# com_board.net
KiCad netlist of a schematic drawn in EAGLE
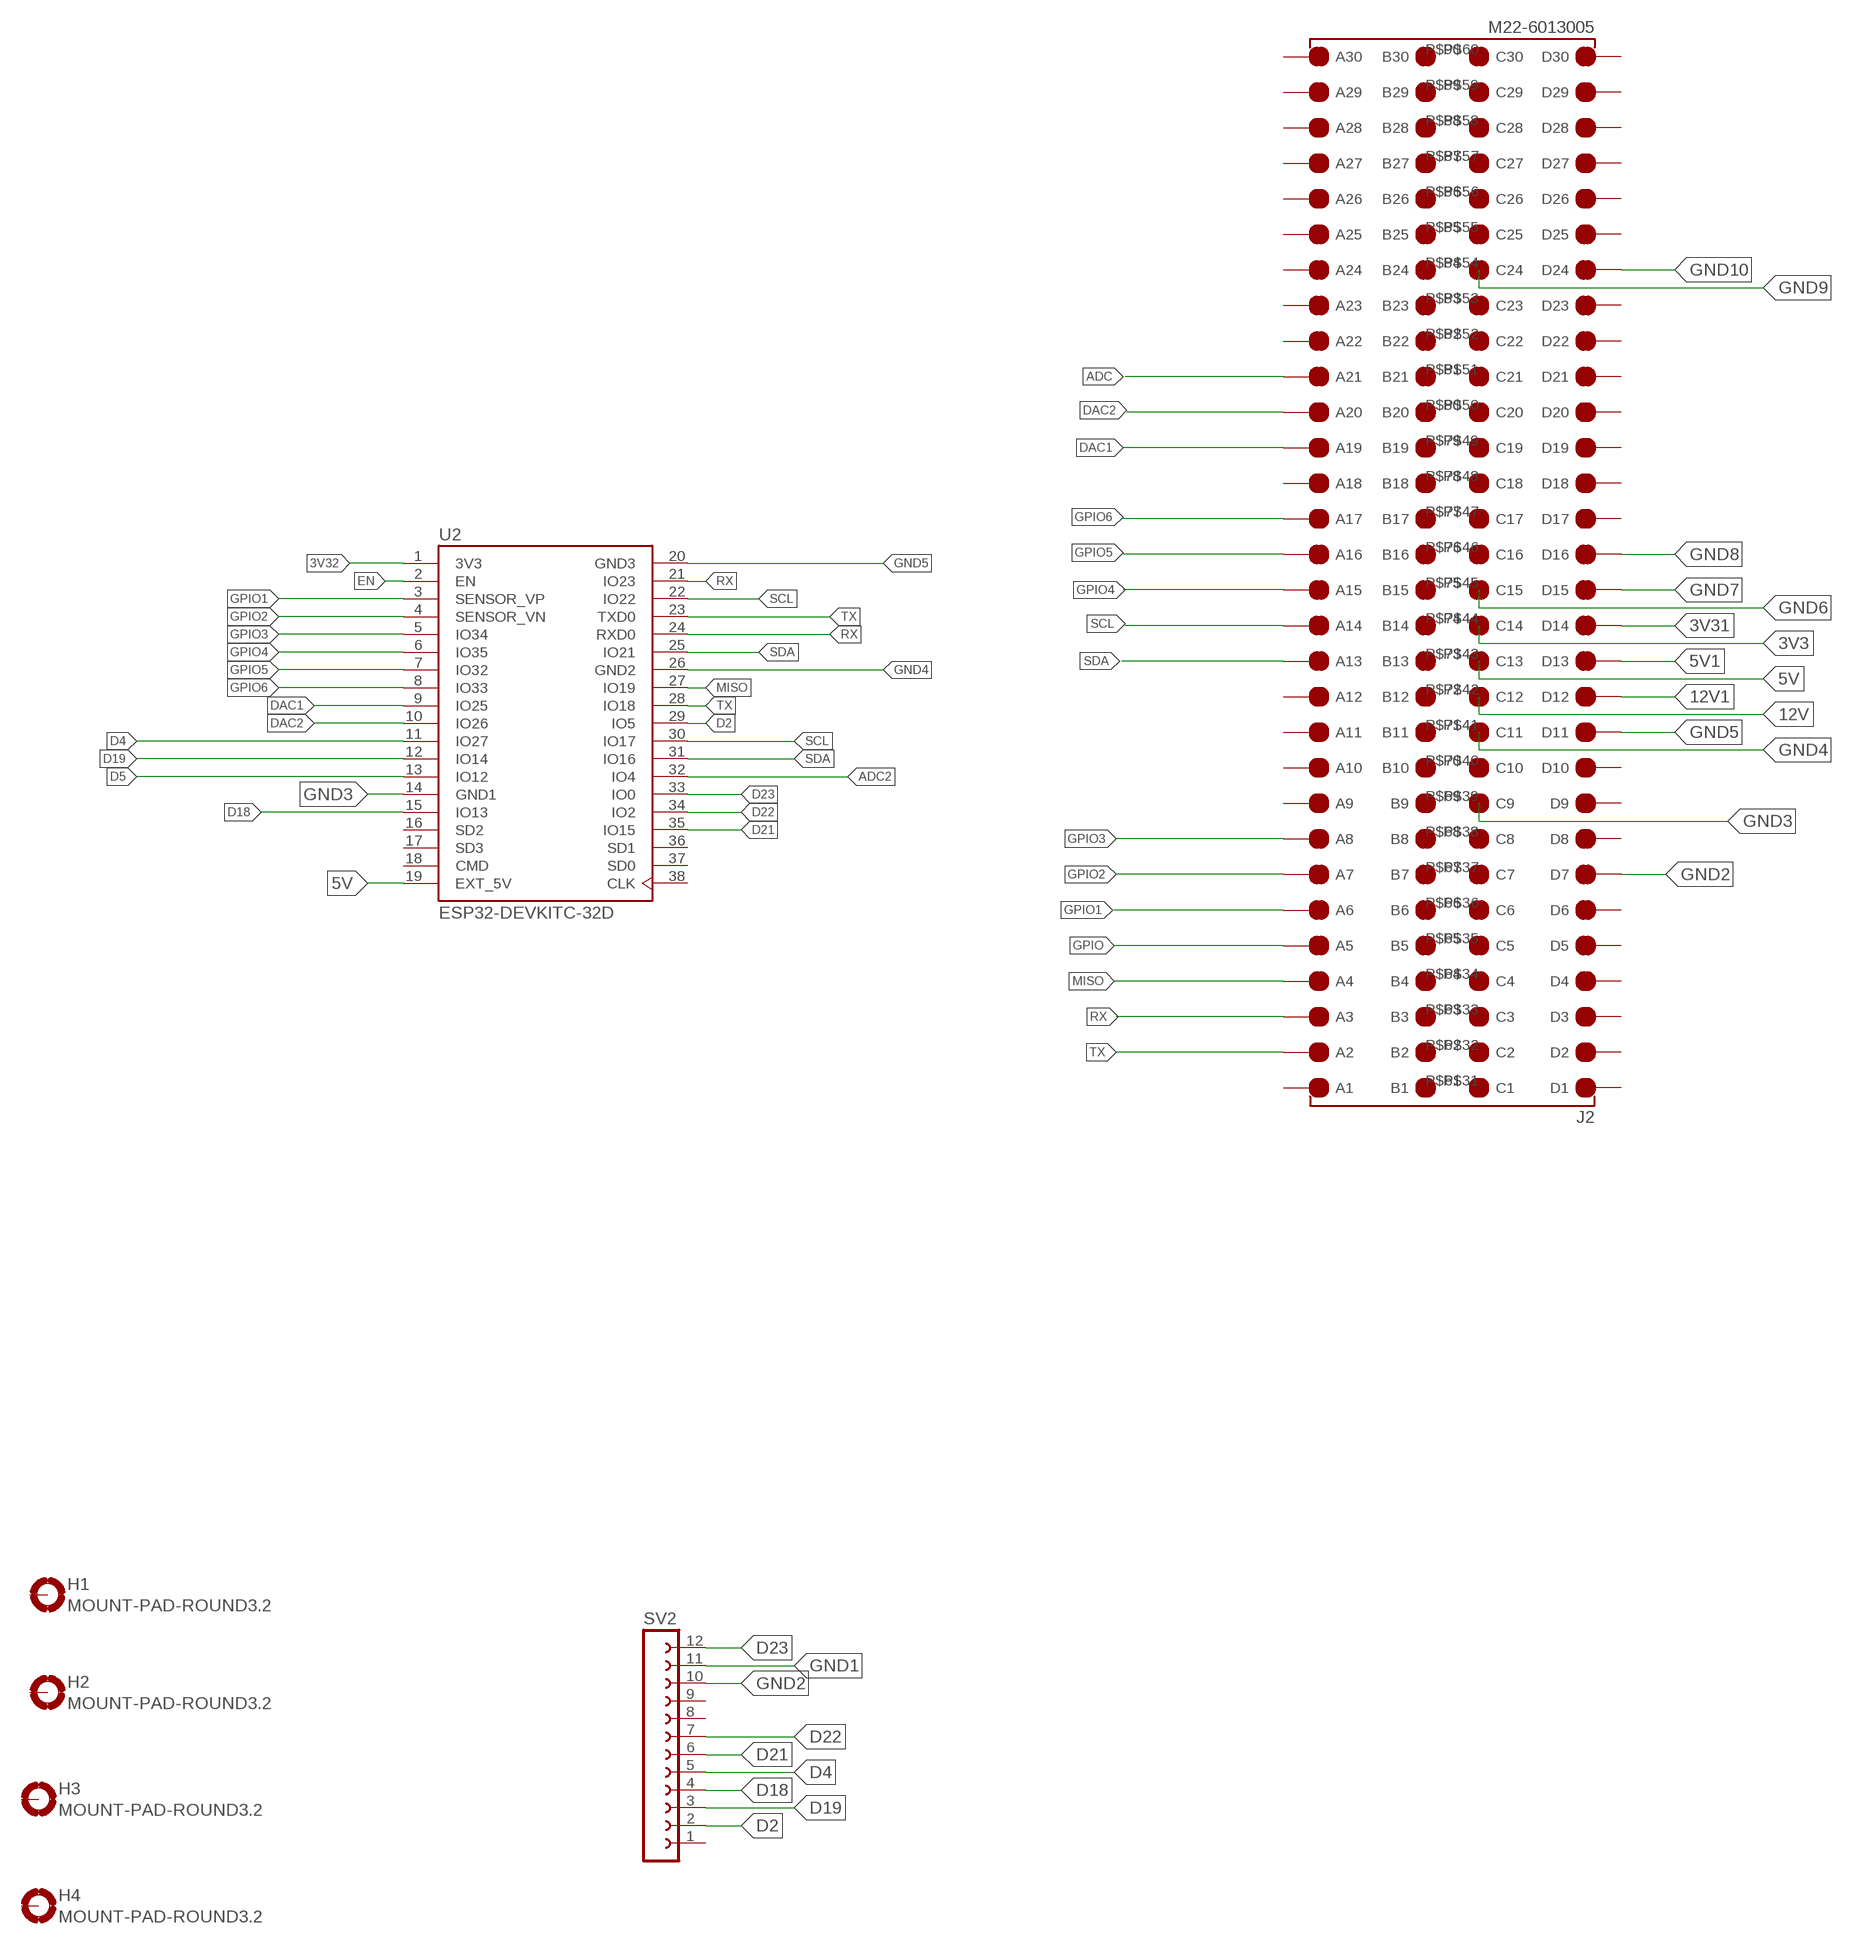
[diagram p0: schematic, sheet 1]

(export (version "E")
  (design (tool "Eeschema 10.0.6"))
  (components
    (comp (ref "H1")
      (value "MOUNT-PAD-ROUND3.2")
      (footprint "eagle-import:3,2-PAD")
      (libsource (lib "eagle-import") (part "MOUNT-PAD-ROUND3.2"))
    )
    (comp (ref "H2")
      (value "MOUNT-PAD-ROUND3.2")
      (footprint "eagle-import:3,2-PAD")
      (libsource (lib "eagle-import") (part "MOUNT-PAD-ROUND3.2"))
    )
    (comp (ref "H3")
      (value "MOUNT-PAD-ROUND3.2")
      (footprint "eagle-import:3,2-PAD")
      (libsource (lib "eagle-import") (part "MOUNT-PAD-ROUND3.2"))
    )
    (comp (ref "H4")
      (value "MOUNT-PAD-ROUND3.2")
      (footprint "eagle-import:3,2-PAD")
      (libsource (lib "eagle-import") (part "MOUNT-PAD-ROUND3.2"))
    )
    (comp (ref "J2")
      (value "M22-6013005")
      (footprint "eagle-import:RHDR120W55P200_4X30_6020X820X9")
      (libsource (lib "eagle-import") (part "M22-6013005"))
    )
    (comp (ref "SV2")
      (value "FE12-1")
      (footprint "eagle-import:FE12")
      (libsource (lib "eagle-import") (part "FE12-1"))
    )
    (comp (ref "U2")
      (value "ESP32-DEVKITC-32D")
      (footprint "eagle-import:MODULE_ESP32-DEVKITC-32D")
      (fields (field (name "MF") "Espressif Systems"))
      (libsource (lib "eagle-import") (part "ESP32-DEVKITC-32D"))
    )
  )
  (nets
    (net (code "1") (name "3V3") (class "Default")
      (node (ref "J2") (pin "P$44") (pinfunction "C14_P$44") (pintype "passive"))
    )
    (net (code "2") (name "3V31") (class "Default")
      (node (ref "J2") (pin "P$14") (pinfunction "D14_P$14") (pintype "passive"))
    )
    (net (code "3") (name "3V32") (class "Default")
      (node (ref "U2") (pin "1") (pinfunction "3V3_1") (pintype "power_in"))
    )
    (net (code "4") (name "5V") (class "Default")
      (node (ref "J2") (pin "P$43") (pinfunction "C13_P$43") (pintype "passive"))
      (node (ref "U2") (pin "19") (pinfunction "EXT_5V_19") (pintype "power_in"))
    )
    (net (code "5") (name "5V1") (class "Default")
      (node (ref "J2") (pin "P$13") (pinfunction "D13_P$13") (pintype "passive"))
    )
    (net (code "6") (name "12V") (class "Default")
      (node (ref "J2") (pin "P$42") (pinfunction "C12_P$42") (pintype "passive"))
    )
    (net (code "7") (name "12V1") (class "Default")
      (node (ref "J2") (pin "P$12") (pinfunction "D12_P$12") (pintype "passive"))
    )
    (net (code "8") (name "ADC") (class "Default")
      (node (ref "J2") (pin "P$111") (pinfunction "A21_P$111") (pintype "passive"))
    )
    (net (code "9") (name "ADC2") (class "Default")
      (node (ref "U2") (pin "32") (pinfunction "IO4_32") (pintype "bidirectional"))
    )
    (net (code "10") (name "D2") (class "Default")
      (node (ref "SV2") (pin "2") (pinfunction "2_2") (pintype "passive"))
      (node (ref "U2") (pin "29") (pinfunction "IO5_29") (pintype "bidirectional"))
    )
    (net (code "11") (name "D4") (class "Default")
      (node (ref "SV2") (pin "5") (pinfunction "5_5") (pintype "passive"))
      (node (ref "U2") (pin "11") (pinfunction "IO27_11") (pintype "bidirectional"))
    )
    (net (code "12") (name "D5") (class "Default")
      (node (ref "U2") (pin "13") (pinfunction "IO12_13") (pintype "bidirectional"))
    )
    (net (code "13") (name "D18") (class "Default")
      (node (ref "SV2") (pin "4") (pinfunction "4_4") (pintype "passive"))
      (node (ref "U2") (pin "15") (pinfunction "IO13_15") (pintype "bidirectional"))
    )
    (net (code "14") (name "D19") (class "Default")
      (node (ref "SV2") (pin "3") (pinfunction "3_3") (pintype "passive"))
      (node (ref "U2") (pin "12") (pinfunction "IO14_12") (pintype "bidirectional"))
    )
    (net (code "15") (name "D21") (class "Default")
      (node (ref "SV2") (pin "6") (pinfunction "6_6") (pintype "passive"))
      (node (ref "U2") (pin "35") (pinfunction "IO15_35") (pintype "bidirectional"))
    )
    (net (code "16") (name "D22") (class "Default")
      (node (ref "SV2") (pin "7") (pinfunction "7_7") (pintype "passive"))
      (node (ref "U2") (pin "34") (pinfunction "IO2_34") (pintype "bidirectional"))
    )
    (net (code "17") (name "D23") (class "Default")
      (node (ref "SV2") (pin "12") (pinfunction "12_12") (pintype "passive"))
      (node (ref "U2") (pin "33") (pinfunction "IO0_33") (pintype "bidirectional"))
    )
    (net (code "18") (name "DAC1") (class "Default")
      (node (ref "J2") (pin "P$109") (pinfunction "A19_P$109") (pintype "passive"))
      (node (ref "U2") (pin "9") (pinfunction "IO25_9") (pintype "bidirectional"))
    )
    (net (code "19") (name "DAC2") (class "Default")
      (node (ref "J2") (pin "P$110") (pinfunction "A20_P$110") (pintype "passive"))
      (node (ref "U2") (pin "10") (pinfunction "IO26_10") (pintype "bidirectional"))
    )
    (net (code "20") (name "EN") (class "Default")
      (node (ref "U2") (pin "2") (pinfunction "EN_2") (pintype "input"))
    )
    (net (code "21") (name "GND1") (class "Default")
      (node (ref "SV2") (pin "11") (pinfunction "11_11") (pintype "passive"))
    )
    (net (code "22") (name "GND2") (class "Default")
      (node (ref "J2") (pin "P$7") (pinfunction "D7_P$7") (pintype "passive"))
      (node (ref "SV2") (pin "10") (pinfunction "10_10") (pintype "passive"))
    )
    (net (code "23") (name "GND3") (class "Default")
      (node (ref "J2") (pin "P$39") (pinfunction "C9_P$39") (pintype "passive"))
      (node (ref "U2") (pin "14") (pinfunction "GND1_14") (pintype "power_in"))
    )
    (net (code "24") (name "GND4") (class "Default")
      (node (ref "J2") (pin "P$41") (pinfunction "C11_P$41") (pintype "passive"))
      (node (ref "U2") (pin "26") (pinfunction "GND2_26") (pintype "power_in"))
    )
    (net (code "25") (name "GND5") (class "Default")
      (node (ref "J2") (pin "P$11") (pinfunction "D11_P$11") (pintype "passive"))
      (node (ref "U2") (pin "20") (pinfunction "GND3_20") (pintype "power_in"))
    )
    (net (code "26") (name "GND6") (class "Default")
      (node (ref "J2") (pin "P$45") (pinfunction "C15_P$45") (pintype "passive"))
    )
    (net (code "27") (name "GND7") (class "Default")
      (node (ref "J2") (pin "P$15") (pinfunction "D15_P$15") (pintype "passive"))
    )
    (net (code "28") (name "GND8") (class "Default")
      (node (ref "J2") (pin "P$16") (pinfunction "D16_P$16") (pintype "passive"))
    )
    (net (code "29") (name "GND9") (class "Default")
      (node (ref "J2") (pin "P$54") (pinfunction "C24_P$54") (pintype "passive"))
    )
    (net (code "30") (name "GND10") (class "Default")
      (node (ref "J2") (pin "P$24") (pinfunction "D24_P$24") (pintype "passive"))
    )
    (net (code "31") (name "GPIO") (class "Default")
      (node (ref "J2") (pin "P$95") (pinfunction "A5_P$95") (pintype "passive"))
    )
    (net (code "32") (name "GPIO1") (class "Default")
      (node (ref "J2") (pin "P$96") (pinfunction "A6_P$96") (pintype "passive"))
      (node (ref "U2") (pin "3") (pinfunction "SENSOR_VP_3") (pintype "input"))
    )
    (net (code "33") (name "GPIO2") (class "Default")
      (node (ref "J2") (pin "P$97") (pinfunction "A7_P$97") (pintype "passive"))
      (node (ref "U2") (pin "4") (pinfunction "SENSOR_VN_4") (pintype "input"))
    )
    (net (code "34") (name "GPIO3") (class "Default")
      (node (ref "J2") (pin "P$98") (pinfunction "A8_P$98") (pintype "passive"))
      (node (ref "U2") (pin "5") (pinfunction "IO34_5") (pintype "bidirectional"))
    )
    (net (code "35") (name "GPIO4") (class "Default")
      (node (ref "J2") (pin "P$105") (pinfunction "A15_P$105") (pintype "passive"))
      (node (ref "U2") (pin "6") (pinfunction "IO35_6") (pintype "bidirectional"))
    )
    (net (code "36") (name "GPIO5") (class "Default")
      (node (ref "J2") (pin "P$106") (pinfunction "A16_P$106") (pintype "passive"))
      (node (ref "U2") (pin "7") (pinfunction "IO32_7") (pintype "bidirectional"))
    )
    (net (code "37") (name "GPIO6") (class "Default")
      (node (ref "J2") (pin "P$107") (pinfunction "A17_P$107") (pintype "passive"))
      (node (ref "U2") (pin "8") (pinfunction "IO33_8") (pintype "bidirectional"))
    )
    (net (code "38") (name "MISO") (class "Default")
      (node (ref "J2") (pin "P$94") (pinfunction "A4_P$94") (pintype "passive"))
      (node (ref "U2") (pin "27") (pinfunction "IO19_27") (pintype "bidirectional"))
    )
    (net (code "39") (name "RX") (class "Default")
      (node (ref "J2") (pin "P$93") (pinfunction "A3_P$93") (pintype "passive"))
      (node (ref "U2") (pin "21") (pinfunction "IO23_21") (pintype "bidirectional"))
      (node (ref "U2") (pin "24") (pinfunction "RXD0_24") (pintype "input"))
    )
    (net (code "40") (name "SCL") (class "Default")
      (node (ref "J2") (pin "P$104") (pinfunction "A14_P$104") (pintype "passive"))
      (node (ref "U2") (pin "22") (pinfunction "IO22_22") (pintype "bidirectional"))
      (node (ref "U2") (pin "30") (pinfunction "IO17_30") (pintype "bidirectional"))
    )
    (net (code "41") (name "SDA") (class "Default")
      (node (ref "J2") (pin "P$103") (pinfunction "A13_P$103") (pintype "passive"))
      (node (ref "U2") (pin "25") (pinfunction "IO21_25") (pintype "bidirectional"))
      (node (ref "U2") (pin "31") (pinfunction "IO16_31") (pintype "bidirectional"))
    )
    (net (code "42") (name "TX") (class "Default")
      (node (ref "J2") (pin "P$92") (pinfunction "A2_P$92") (pintype "passive"))
      (node (ref "U2") (pin "23") (pinfunction "TXD0_23") (pintype "output"))
      (node (ref "U2") (pin "28") (pinfunction "IO18_28") (pintype "bidirectional"))
    )
    (net (code "43") (name "unconnected-(H1-MOUNT-PadB3,2)") (class "Default")
      (node (ref "H1") (pin "B3,2") (pinfunction "MOUNT_B3,2") (pintype "passive"))
    )
    (net (code "44") (name "unconnected-(H2-MOUNT-PadB3,2)") (class "Default")
      (node (ref "H2") (pin "B3,2") (pinfunction "MOUNT_B3,2") (pintype "passive"))
    )
    (net (code "45") (name "unconnected-(H3-MOUNT-PadB3,2)") (class "Default")
      (node (ref "H3") (pin "B3,2") (pinfunction "MOUNT_B3,2") (pintype "passive"))
    )
    (net (code "46") (name "unconnected-(H4-MOUNT-PadB3,2)") (class "Default")
      (node (ref "H4") (pin "B3,2") (pinfunction "MOUNT_B3,2") (pintype "passive"))
    )
    (net (code "47") (name "unconnected-(J2-A1-PadP$91)") (class "Default")
      (node (ref "J2") (pin "P$91") (pinfunction "A1_P$91") (pintype "passive"))
    )
    (net (code "48") (name "unconnected-(J2-A9-PadP$99)") (class "Default")
      (node (ref "J2") (pin "P$99") (pinfunction "A9_P$99") (pintype "passive"))
    )
    (net (code "49") (name "unconnected-(J2-A10-PadP$100)") (class "Default")
      (node (ref "J2") (pin "P$100") (pinfunction "A10_P$100") (pintype "passive"))
    )
    (net (code "50") (name "unconnected-(J2-A11-PadP$101)") (class "Default")
      (node (ref "J2") (pin "P$101") (pinfunction "A11_P$101") (pintype "passive"))
    )
    (net (code "51") (name "unconnected-(J2-A12-PadP$102)") (class "Default")
      (node (ref "J2") (pin "P$102") (pinfunction "A12_P$102") (pintype "passive"))
    )
    (net (code "52") (name "unconnected-(J2-A18-PadP$108)") (class "Default")
      (node (ref "J2") (pin "P$108") (pinfunction "A18_P$108") (pintype "passive"))
    )
    (net (code "53") (name "unconnected-(J2-A22-PadP$112)") (class "Default")
      (node (ref "J2") (pin "P$112") (pinfunction "A22_P$112") (pintype "passive"))
    )
    (net (code "54") (name "unconnected-(J2-A23-PadP$113)") (class "Default")
      (node (ref "J2") (pin "P$113") (pinfunction "A23_P$113") (pintype "passive"))
    )
    (net (code "55") (name "unconnected-(J2-A24-PadP$114)") (class "Default")
      (node (ref "J2") (pin "P$114") (pinfunction "A24_P$114") (pintype "passive"))
    )
    (net (code "56") (name "unconnected-(J2-A25-PadP$115)") (class "Default")
      (node (ref "J2") (pin "P$115") (pinfunction "A25_P$115") (pintype "passive"))
    )
    (net (code "57") (name "unconnected-(J2-A26-PadP$116)") (class "Default")
      (node (ref "J2") (pin "P$116") (pinfunction "A26_P$116") (pintype "passive"))
    )
    (net (code "58") (name "unconnected-(J2-A27-PadP$117)") (class "Default")
      (node (ref "J2") (pin "P$117") (pinfunction "A27_P$117") (pintype "passive"))
    )
    (net (code "59") (name "unconnected-(J2-A28-PadP$118)") (class "Default")
      (node (ref "J2") (pin "P$118") (pinfunction "A28_P$118") (pintype "passive"))
    )
    (net (code "60") (name "unconnected-(J2-A29-PadP$119)") (class "Default")
      (node (ref "J2") (pin "P$119") (pinfunction "A29_P$119") (pintype "passive"))
    )
    (net (code "61") (name "unconnected-(J2-A30-PadP$120)") (class "Default")
      (node (ref "J2") (pin "P$120") (pinfunction "A30_P$120") (pintype "passive"))
    )
    (net (code "62") (name "unconnected-(J2-B1-PadP$61)") (class "Default")
      (node (ref "J2") (pin "P$61") (pinfunction "B1_P$61") (pintype "passive"))
    )
    (net (code "63") (name "unconnected-(J2-B2-PadP$62)") (class "Default")
      (node (ref "J2") (pin "P$62") (pinfunction "B2_P$62") (pintype "passive"))
    )
    (net (code "64") (name "unconnected-(J2-B3-PadP$63)") (class "Default")
      (node (ref "J2") (pin "P$63") (pinfunction "B3_P$63") (pintype "passive"))
    )
    (net (code "65") (name "unconnected-(J2-B4-PadP$64)") (class "Default")
      (node (ref "J2") (pin "P$64") (pinfunction "B4_P$64") (pintype "passive"))
    )
    (net (code "66") (name "unconnected-(J2-B5-PadP$65)") (class "Default")
      (node (ref "J2") (pin "P$65") (pinfunction "B5_P$65") (pintype "passive"))
    )
    (net (code "67") (name "unconnected-(J2-B6-PadP$66)") (class "Default")
      (node (ref "J2") (pin "P$66") (pinfunction "B6_P$66") (pintype "passive"))
    )
    (net (code "68") (name "unconnected-(J2-B7-PadP$67)") (class "Default")
      (node (ref "J2") (pin "P$67") (pinfunction "B7_P$67") (pintype "passive"))
    )
    (net (code "69") (name "unconnected-(J2-B8-PadP$68)") (class "Default")
      (node (ref "J2") (pin "P$68") (pinfunction "B8_P$68") (pintype "passive"))
    )
    (net (code "70") (name "unconnected-(J2-B9-PadP$69)") (class "Default")
      (node (ref "J2") (pin "P$69") (pinfunction "B9_P$69") (pintype "passive"))
    )
    (net (code "71") (name "unconnected-(J2-B10-PadP$70)") (class "Default")
      (node (ref "J2") (pin "P$70") (pinfunction "B10_P$70") (pintype "passive"))
    )
    (net (code "72") (name "unconnected-(J2-B11-PadP$71)") (class "Default")
      (node (ref "J2") (pin "P$71") (pinfunction "B11_P$71") (pintype "passive"))
    )
    (net (code "73") (name "unconnected-(J2-B12-PadP$72)") (class "Default")
      (node (ref "J2") (pin "P$72") (pinfunction "B12_P$72") (pintype "passive"))
    )
    (net (code "74") (name "unconnected-(J2-B13-PadP$73)") (class "Default")
      (node (ref "J2") (pin "P$73") (pinfunction "B13_P$73") (pintype "passive"))
    )
    (net (code "75") (name "unconnected-(J2-B14-PadP$74)") (class "Default")
      (node (ref "J2") (pin "P$74") (pinfunction "B14_P$74") (pintype "passive"))
    )
    (net (code "76") (name "unconnected-(J2-B15-PadP$75)") (class "Default")
      (node (ref "J2") (pin "P$75") (pinfunction "B15_P$75") (pintype "passive"))
    )
    (net (code "77") (name "unconnected-(J2-B16-PadP$76)") (class "Default")
      (node (ref "J2") (pin "P$76") (pinfunction "B16_P$76") (pintype "passive"))
    )
    (net (code "78") (name "unconnected-(J2-B17-PadP$77)") (class "Default")
      (node (ref "J2") (pin "P$77") (pinfunction "B17_P$77") (pintype "passive"))
    )
    (net (code "79") (name "unconnected-(J2-B18-PadP$78)") (class "Default")
      (node (ref "J2") (pin "P$78") (pinfunction "B18_P$78") (pintype "passive"))
    )
    (net (code "80") (name "unconnected-(J2-B19-PadP$79)") (class "Default")
      (node (ref "J2") (pin "P$79") (pinfunction "B19_P$79") (pintype "passive"))
    )
    (net (code "81") (name "unconnected-(J2-B20-PadP$80)") (class "Default")
      (node (ref "J2") (pin "P$80") (pinfunction "B20_P$80") (pintype "passive"))
    )
    (net (code "82") (name "unconnected-(J2-B21-PadP$81)") (class "Default")
      (node (ref "J2") (pin "P$81") (pinfunction "B21_P$81") (pintype "passive"))
    )
    (net (code "83") (name "unconnected-(J2-B22-PadP$82)") (class "Default")
      (node (ref "J2") (pin "P$82") (pinfunction "B22_P$82") (pintype "passive"))
    )
    (net (code "84") (name "unconnected-(J2-B23-PadP$83)") (class "Default")
      (node (ref "J2") (pin "P$83") (pinfunction "B23_P$83") (pintype "passive"))
    )
    (net (code "85") (name "unconnected-(J2-B24-PadP$84)") (class "Default")
      (node (ref "J2") (pin "P$84") (pinfunction "B24_P$84") (pintype "passive"))
    )
    (net (code "86") (name "unconnected-(J2-B25-PadP$85)") (class "Default")
      (node (ref "J2") (pin "P$85") (pinfunction "B25_P$85") (pintype "passive"))
    )
    (net (code "87") (name "unconnected-(J2-B26-PadP$86)") (class "Default")
      (node (ref "J2") (pin "P$86") (pinfunction "B26_P$86") (pintype "passive"))
    )
    (net (code "88") (name "unconnected-(J2-B27-PadP$87)") (class "Default")
      (node (ref "J2") (pin "P$87") (pinfunction "B27_P$87") (pintype "passive"))
    )
    (net (code "89") (name "unconnected-(J2-B28-PadP$88)") (class "Default")
      (node (ref "J2") (pin "P$88") (pinfunction "B28_P$88") (pintype "passive"))
    )
    (net (code "90") (name "unconnected-(J2-B29-PadP$89)") (class "Default")
      (node (ref "J2") (pin "P$89") (pinfunction "B29_P$89") (pintype "passive"))
    )
    (net (code "91") (name "unconnected-(J2-B30-PadP$90)") (class "Default")
      (node (ref "J2") (pin "P$90") (pinfunction "B30_P$90") (pintype "passive"))
    )
    (net (code "92") (name "unconnected-(J2-C1-PadP$31)") (class "Default")
      (node (ref "J2") (pin "P$31") (pinfunction "C1_P$31") (pintype "passive"))
    )
    (net (code "93") (name "unconnected-(J2-C2-PadP$32)") (class "Default")
      (node (ref "J2") (pin "P$32") (pinfunction "C2_P$32") (pintype "passive"))
    )
    (net (code "94") (name "unconnected-(J2-C3-PadP$33)") (class "Default")
      (node (ref "J2") (pin "P$33") (pinfunction "C3_P$33") (pintype "passive"))
    )
    (net (code "95") (name "unconnected-(J2-C4-PadP$34)") (class "Default")
      (node (ref "J2") (pin "P$34") (pinfunction "C4_P$34") (pintype "passive"))
    )
    (net (code "96") (name "unconnected-(J2-C5-PadP$35)") (class "Default")
      (node (ref "J2") (pin "P$35") (pinfunction "C5_P$35") (pintype "passive"))
    )
    (net (code "97") (name "unconnected-(J2-C6-PadP$36)") (class "Default")
      (node (ref "J2") (pin "P$36") (pinfunction "C6_P$36") (pintype "passive"))
    )
    (net (code "98") (name "unconnected-(J2-C7-PadP$37)") (class "Default")
      (node (ref "J2") (pin "P$37") (pinfunction "C7_P$37") (pintype "passive"))
    )
    (net (code "99") (name "unconnected-(J2-C8-PadP$38)") (class "Default")
      (node (ref "J2") (pin "P$38") (pinfunction "C8_P$38") (pintype "passive"))
    )
    (net (code "100") (name "unconnected-(J2-C10-PadP$40)") (class "Default")
      (node (ref "J2") (pin "P$40") (pinfunction "C10_P$40") (pintype "passive"))
    )
    (net (code "101") (name "unconnected-(J2-C16-PadP$46)") (class "Default")
      (node (ref "J2") (pin "P$46") (pinfunction "C16_P$46") (pintype "passive"))
    )
    (net (code "102") (name "unconnected-(J2-C17-PadP$47)") (class "Default")
      (node (ref "J2") (pin "P$47") (pinfunction "C17_P$47") (pintype "passive"))
    )
    (net (code "103") (name "unconnected-(J2-C18-PadP$48)") (class "Default")
      (node (ref "J2") (pin "P$48") (pinfunction "C18_P$48") (pintype "passive"))
    )
    (net (code "104") (name "unconnected-(J2-C19-PadP$49)") (class "Default")
      (node (ref "J2") (pin "P$49") (pinfunction "C19_P$49") (pintype "passive"))
    )
    (net (code "105") (name "unconnected-(J2-C20-PadP$50)") (class "Default")
      (node (ref "J2") (pin "P$50") (pinfunction "C20_P$50") (pintype "passive"))
    )
    (net (code "106") (name "unconnected-(J2-C21-PadP$51)") (class "Default")
      (node (ref "J2") (pin "P$51") (pinfunction "C21_P$51") (pintype "passive"))
    )
    (net (code "107") (name "unconnected-(J2-C22-PadP$52)") (class "Default")
      (node (ref "J2") (pin "P$52") (pinfunction "C22_P$52") (pintype "passive"))
    )
    (net (code "108") (name "unconnected-(J2-C23-PadP$53)") (class "Default")
      (node (ref "J2") (pin "P$53") (pinfunction "C23_P$53") (pintype "passive"))
    )
    (net (code "109") (name "unconnected-(J2-C25-PadP$55)") (class "Default")
      (node (ref "J2") (pin "P$55") (pinfunction "C25_P$55") (pintype "passive"))
    )
    (net (code "110") (name "unconnected-(J2-C26-PadP$56)") (class "Default")
      (node (ref "J2") (pin "P$56") (pinfunction "C26_P$56") (pintype "passive"))
    )
    (net (code "111") (name "unconnected-(J2-C27-PadP$57)") (class "Default")
      (node (ref "J2") (pin "P$57") (pinfunction "C27_P$57") (pintype "passive"))
    )
    (net (code "112") (name "unconnected-(J2-C28-PadP$58)") (class "Default")
      (node (ref "J2") (pin "P$58") (pinfunction "C28_P$58") (pintype "passive"))
    )
    (net (code "113") (name "unconnected-(J2-C29-PadP$59)") (class "Default")
      (node (ref "J2") (pin "P$59") (pinfunction "C29_P$59") (pintype "passive"))
    )
    (net (code "114") (name "unconnected-(J2-C30-PadP$60)") (class "Default")
      (node (ref "J2") (pin "P$60") (pinfunction "C30_P$60") (pintype "passive"))
    )
    (net (code "115") (name "unconnected-(J2-D1-PadP$1)") (class "Default")
      (node (ref "J2") (pin "P$1") (pinfunction "D1_P$1") (pintype "passive"))
    )
    (net (code "116") (name "unconnected-(J2-D2-PadP$2)") (class "Default")
      (node (ref "J2") (pin "P$2") (pinfunction "D2_P$2") (pintype "passive"))
    )
    (net (code "117") (name "unconnected-(J2-D3-PadP$3)") (class "Default")
      (node (ref "J2") (pin "P$3") (pinfunction "D3_P$3") (pintype "passive"))
    )
    (net (code "118") (name "unconnected-(J2-D4-PadP$4)") (class "Default")
      (node (ref "J2") (pin "P$4") (pinfunction "D4_P$4") (pintype "passive"))
    )
    (net (code "119") (name "unconnected-(J2-D5-PadP$5)") (class "Default")
      (node (ref "J2") (pin "P$5") (pinfunction "D5_P$5") (pintype "passive"))
    )
    (net (code "120") (name "unconnected-(J2-D6-PadP$6)") (class "Default")
      (node (ref "J2") (pin "P$6") (pinfunction "D6_P$6") (pintype "passive"))
    )
    (net (code "121") (name "unconnected-(J2-D8-PadP$8)") (class "Default")
      (node (ref "J2") (pin "P$8") (pinfunction "D8_P$8") (pintype "passive"))
    )
    (net (code "122") (name "unconnected-(J2-D9-PadP$9)") (class "Default")
      (node (ref "J2") (pin "P$9") (pinfunction "D9_P$9") (pintype "passive"))
    )
    (net (code "123") (name "unconnected-(J2-D10-PadP$10)") (class "Default")
      (node (ref "J2") (pin "P$10") (pinfunction "D10_P$10") (pintype "passive"))
    )
    (net (code "124") (name "unconnected-(J2-D17-PadP$17)") (class "Default")
      (node (ref "J2") (pin "P$17") (pinfunction "D17_P$17") (pintype "passive"))
    )
    (net (code "125") (name "unconnected-(J2-D18-PadP$18)") (class "Default")
      (node (ref "J2") (pin "P$18") (pinfunction "D18_P$18") (pintype "passive"))
    )
    (net (code "126") (name "unconnected-(J2-D19-PadP$19)") (class "Default")
      (node (ref "J2") (pin "P$19") (pinfunction "D19_P$19") (pintype "passive"))
    )
    (net (code "127") (name "unconnected-(J2-D20-PadP$20)") (class "Default")
      (node (ref "J2") (pin "P$20") (pinfunction "D20_P$20") (pintype "passive"))
    )
    (net (code "128") (name "unconnected-(J2-D21-PadP$21)") (class "Default")
      (node (ref "J2") (pin "P$21") (pinfunction "D21_P$21") (pintype "passive"))
    )
    (net (code "129") (name "unconnected-(J2-D22-PadP$22)") (class "Default")
      (node (ref "J2") (pin "P$22") (pinfunction "D22_P$22") (pintype "passive"))
    )
    (net (code "130") (name "unconnected-(J2-D23-PadP$23)") (class "Default")
      (node (ref "J2") (pin "P$23") (pinfunction "D23_P$23") (pintype "passive"))
    )
    (net (code "131") (name "unconnected-(J2-D25-PadP$25)") (class "Default")
      (node (ref "J2") (pin "P$25") (pinfunction "D25_P$25") (pintype "passive"))
    )
    (net (code "132") (name "unconnected-(J2-D26-PadP$26)") (class "Default")
      (node (ref "J2") (pin "P$26") (pinfunction "D26_P$26") (pintype "passive"))
    )
    (net (code "133") (name "unconnected-(J2-D27-PadP$27)") (class "Default")
      (node (ref "J2") (pin "P$27") (pinfunction "D27_P$27") (pintype "passive"))
    )
    (net (code "134") (name "unconnected-(J2-D28-PadP$28)") (class "Default")
      (node (ref "J2") (pin "P$28") (pinfunction "D28_P$28") (pintype "passive"))
    )
    (net (code "135") (name "unconnected-(J2-D29-PadP$29)") (class "Default")
      (node (ref "J2") (pin "P$29") (pinfunction "D29_P$29") (pintype "passive"))
    )
    (net (code "136") (name "unconnected-(J2-D30-PadP$30)") (class "Default")
      (node (ref "J2") (pin "P$30") (pinfunction "D30_P$30") (pintype "passive"))
    )
    (net (code "137") (name "unconnected-(SV2-Pad1)") (class "Default")
      (node (ref "SV2") (pin "1") (pinfunction "1_1") (pintype "passive"))
    )
    (net (code "138") (name "unconnected-(SV2-Pad8)") (class "Default")
      (node (ref "SV2") (pin "8") (pinfunction "8_8") (pintype "passive"))
    )
    (net (code "139") (name "unconnected-(SV2-Pad9)") (class "Default")
      (node (ref "SV2") (pin "9") (pinfunction "9_9") (pintype "passive"))
    )
    (net (code "140") (name "unconnected-(U2-CLK-Pad38)") (class "Default")
      (node (ref "U2") (pin "38") (pinfunction "CLK_38") (pintype "input"))
    )
    (net (code "141") (name "unconnected-(U2-CMD-Pad18)") (class "Default")
      (node (ref "U2") (pin "18") (pinfunction "CMD_18") (pintype "bidirectional"))
    )
    (net (code "142") (name "unconnected-(U2-SD0-Pad37)") (class "Default")
      (node (ref "U2") (pin "37") (pinfunction "SD0_37") (pintype "bidirectional"))
    )
    (net (code "143") (name "unconnected-(U2-SD1-Pad36)") (class "Default")
      (node (ref "U2") (pin "36") (pinfunction "SD1_36") (pintype "bidirectional"))
    )
    (net (code "144") (name "unconnected-(U2-SD2-Pad16)") (class "Default")
      (node (ref "U2") (pin "16") (pinfunction "SD2_16") (pintype "bidirectional"))
    )
    (net (code "145") (name "unconnected-(U2-SD3-Pad17)") (class "Default")
      (node (ref "U2") (pin "17") (pinfunction "SD3_17") (pintype "bidirectional"))
    )
  )
)
